# power-path-control.net
KiCad netlist of a schematic drawn in Altium Designer
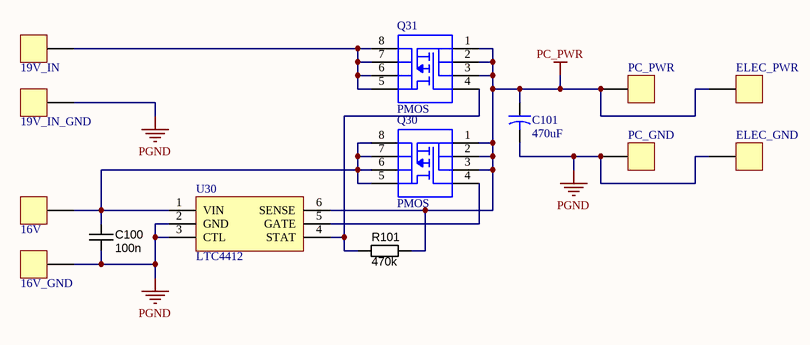
[diagram p0: power-path-control.SchDoc]

(export (version "E")
  (design (tool "Eeschema 10.0.6"))
  (components
    (comp (ref "16V")
      (value "HEADER-1")
      (footprint "POWER-PAD-4x3")
      (libsource (lib "connectors") (part "HEADER-1"))
    )
    (comp (ref "16V_GND")
      (value "HEADER-1")
      (footprint "POWER-PAD-4x3")
      (libsource (lib "connectors") (part "HEADER-1"))
    )
    (comp (ref "19V_IN")
      (value "HEADER-1")
      (footprint "POWER-PAD-4x3")
      (libsource (lib "connectors") (part "HEADER-1"))
    )
    (comp (ref "19V_IN_GND")
      (value "HEADER-1")
      (footprint "POWER-PAD-4x3")
      (libsource (lib "connectors") (part "HEADER-1"))
    )
    (comp (ref "C100")
      (value "100n")
      (footprint "CAPC1608X90N")
      (description "Capacitor SMD Cer 10nF 10% 50V X7R 0603")
      (fields (field (name "TOLERANCE") "±10%"))
      (libsource (lib "PBL - Capacitors") (part "CAPC_10n_0603_X7R_50V_10%"))
    )
    (comp (ref "C101")
      (value "470uF")
      (footprint "CAPR5-4X5")
      (description "Capacitor")
      (fields (field (name "PUBLISHER") "Altium Limited"))
      (libsource (lib "Miscellaneous Devices") (part "Cap2"))
    )
    (comp (ref "ELEC_GND")
      (value "HEADER-1")
      (footprint "POWER-PAD-4x3")
      (libsource (lib "") (part "HEADER-1_1"))
    )
    (comp (ref "ELEC_PWR")
      (value "HEADER-1")
      (footprint "POWER-PAD-4x3")
      (libsource (lib "") (part "HEADER-1_1"))
    )
    (comp (ref "PC_GND")
      (value "HEADER-1")
      (footprint "POWER-PAD-4x3")
      (libsource (lib "") (part "HEADER-1_1"))
    )
    (comp (ref "PC_PWR")
      (value "HEADER-1")
      (footprint "POWER-PAD-4x3")
      (libsource (lib "") (part "HEADER-1_1"))
    )
    (comp (ref "Q30") (value "PMOS") (footprint "SO8") (libsource (lib "misc") (part "PMOS")))
    (comp (ref "Q31") (value "PMOS") (footprint "SO8") (libsource (lib "misc") (part "PMOS")))
    (comp (ref "R101")
      (value "470k")
      (footprint "RESC1608N_ZERO")
      (description "Resistor SMD chip 0.0 Ohm 0.1W 0603")
      (fields (field (name "TOLERANCE") "±5%"))
      (libsource (lib "PBL - Resistors") (part "RES_0R_0603"))
    )
    (comp (ref "U30") (value "LTC4412") (footprint "TSOT-23-6") (libsource (lib "digital") (part "LTC4412")))
  )
  (nets
    (net (code "1") (name "Net-(19V_IN-Pad1)") (class "Default")
      (node (ref "19V_IN") (pin "1") (pinfunction "1_1") (pintype "passive"))
      (node (ref "Q31") (pin "5") (pinfunction "5_5") (pintype "passive"))
      (node (ref "Q31") (pin "6") (pinfunction "6_6") (pintype "passive"))
      (node (ref "Q31") (pin "7") (pinfunction "7_7") (pintype "passive"))
      (node (ref "Q31") (pin "8") (pinfunction "8_8") (pintype "passive"))
    )
    (net (code "2") (name "Net-(U30-GATE)") (class "Default")
      (node (ref "Q30") (pin "4") (pinfunction "4_4") (pintype "passive"))
      (node (ref "U30") (pin "5") (pinfunction "GATE_5") (pintype "passive"))
    )
    (net (code "3") (name "Net-(U30-STAT)") (class "Default")
      (node (ref "Q31") (pin "4") (pinfunction "4_4") (pintype "passive"))
      (node (ref "R101") (pin "2") (pinfunction "2_2") (pintype "passive"))
      (node (ref "U30") (pin "4") (pinfunction "STAT_4") (pintype "passive"))
    )
    (net (code "4") (name "Net-(U30-VIN)") (class "Default")
      (node (ref "16V") (pin "1") (pinfunction "1_1") (pintype "passive"))
      (node (ref "C100") (pin "1") (pintype "passive"))
      (node (ref "Q30") (pin "5") (pinfunction "5_5") (pintype "passive"))
      (node (ref "Q30") (pin "6") (pinfunction "6_6") (pintype "passive"))
      (node (ref "Q30") (pin "7") (pinfunction "7_7") (pintype "passive"))
      (node (ref "Q30") (pin "8") (pinfunction "8_8") (pintype "passive"))
      (node (ref "U30") (pin "1") (pinfunction "VIN_1") (pintype "passive"))
    )
    (net (code "5") (name "PC_PWR") (class "Default")
      (node (ref "C101") (pin "1") (pinfunction "1_1") (pintype "passive"))
      (node (ref "ELEC_PWR") (pin "1") (pinfunction "1_1") (pintype "passive"))
      (node (ref "PC_PWR") (pin "1") (pinfunction "1_1") (pintype "passive"))
      (node (ref "Q30") (pin "1") (pinfunction "1_1") (pintype "passive"))
      (node (ref "Q30") (pin "2") (pinfunction "2_2") (pintype "passive"))
      (node (ref "Q30") (pin "3") (pinfunction "3_3") (pintype "passive"))
      (node (ref "Q31") (pin "1") (pinfunction "1_1") (pintype "passive"))
      (node (ref "Q31") (pin "2") (pinfunction "2_2") (pintype "passive"))
      (node (ref "Q31") (pin "3") (pinfunction "3_3") (pintype "passive"))
      (node (ref "R101") (pin "1") (pinfunction "1_1") (pintype "passive"))
      (node (ref "U30") (pin "6") (pinfunction "SENSE_6") (pintype "passive"))
    )
    (net (code "6") (name "PGND") (class "Default")
      (node (ref "16V_GND") (pin "1") (pinfunction "1_1") (pintype "passive"))
      (node (ref "19V_IN_GND") (pin "1") (pinfunction "1_1") (pintype "passive"))
      (node (ref "C100") (pin "2") (pintype "passive"))
      (node (ref "C101") (pin "2") (pinfunction "2_2") (pintype "passive"))
      (node (ref "ELEC_GND") (pin "1") (pinfunction "1_1") (pintype "passive"))
      (node (ref "PC_GND") (pin "1") (pinfunction "1_1") (pintype "passive"))
      (node (ref "U30") (pin "2") (pinfunction "GND_2") (pintype "passive"))
      (node (ref "U30") (pin "3") (pinfunction "CTL_3") (pintype "passive"))
    )
  )
)
